# Sensor.net
KiCad netlist of a schematic drawn in Altium Designer
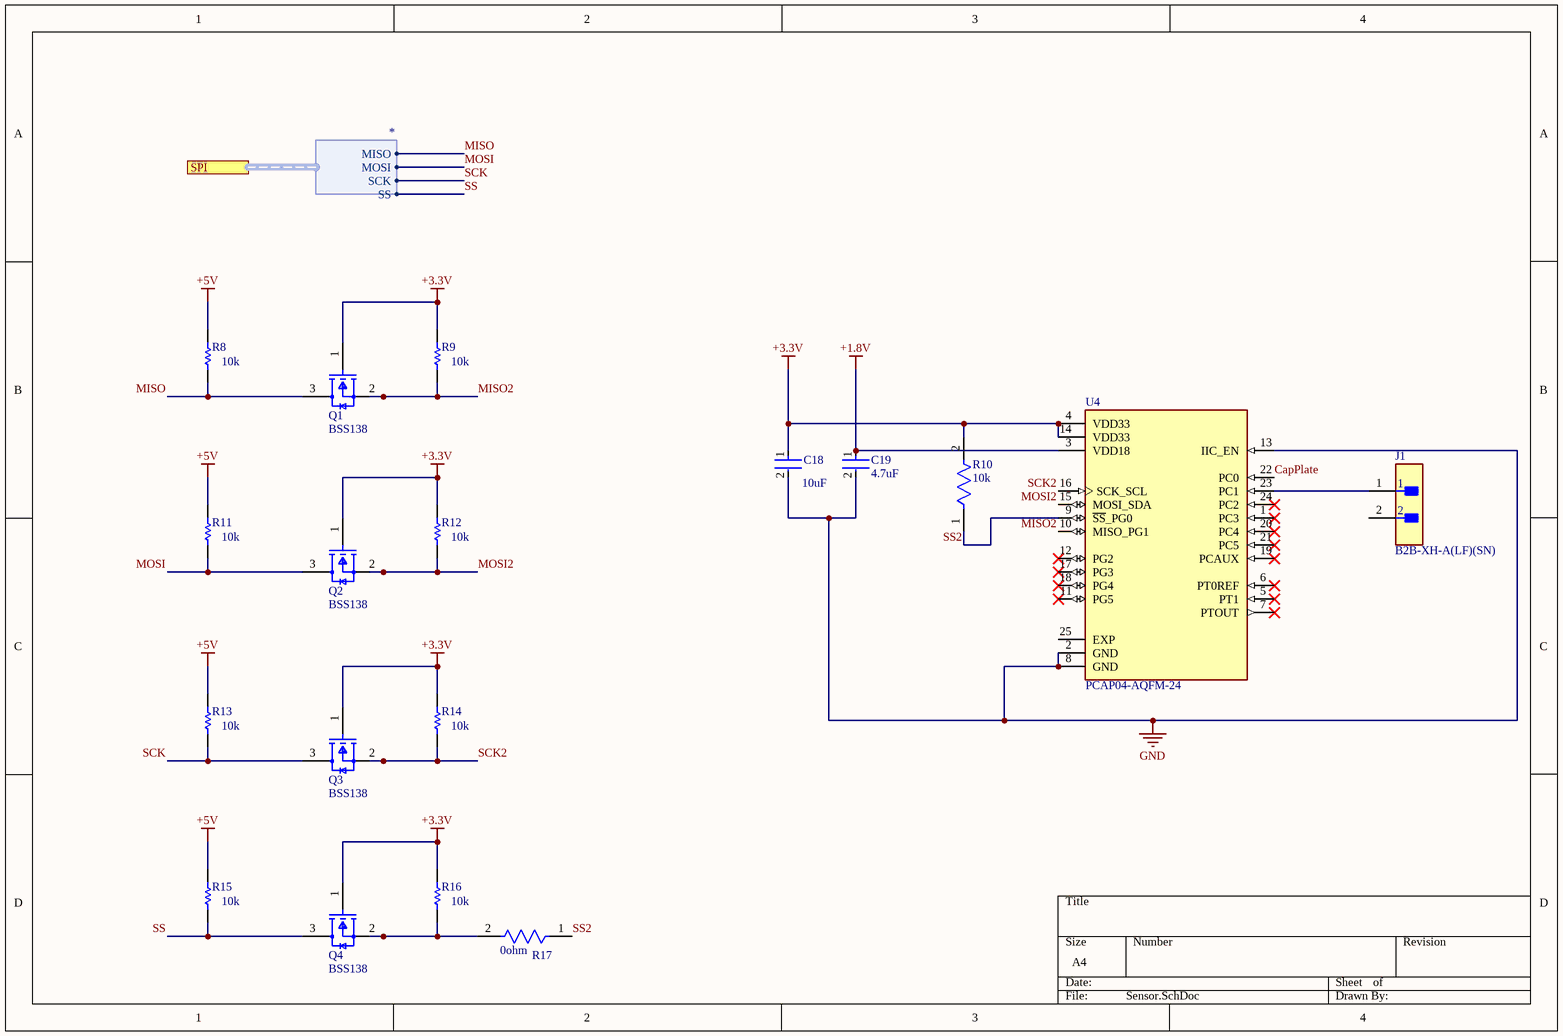
[diagram p0: Sensor.SchDoc]

(export (version "E")
  (design (tool "Eeschema 10.0.6"))
  (components
    (comp (ref "C18")
      (value "C0805C106K8PACTU")
      (footprint "FP-C0805C-DG-MFG")
      (description "CAP CER 10UF 10V X5R 0805")
      (fields
        (field (name "TOLERANCE") "10%")
        (field (name "MANUFACTURER") "Kemet")
        (field (name "CAPACITANCE") "10uF")
      )
      (libsource (lib "Altium Content Vault") (part "11868f565c42a9108669ba33697ecf6"))
    )
    (comp (ref "C19")
      (value "4.7uF")
      (footprint "FP-C0805C475K8PACTU-MFG")
      (description "CAP CER 4.7UF 10V X5R 0805")
      (fields (field (name "TOLERANCE") "10%") (field (name "VOLTAGE") "10V"))
      (libsource (lib "Altium Content Vault") (part "e9c51b7dd13d4faca003ae77663ab08"))
    )
    (comp (ref "J1")
      (value "B2B-XH-A(LF)(SN)")
      (footprint "FP-B2B-XH-A_LF_SN-MFG")
      (description "CONN HEADER VERT 2POS 2.5MM")
      (libsource (lib "Altium Content Vault") (part "3bc925449376181038e59eaffc5286c"))
    )
    (comp (ref "Q1")
      (value "BSS138")
      (footprint "FP-318-08-IPC_B")
      (description "MOSFET N-CH 50V 220MA SOT-23")
      (libsource (lib "Altium Content Vault") (part "3b9c635fedb024a5347a57b145af9cc"))
    )
    (comp (ref "Q2")
      (value "BSS138")
      (footprint "FP-318-08-IPC_B")
      (description "MOSFET N-CH 50V 220MA SOT-23")
      (libsource (lib "Altium Content Vault") (part "3b9c635fedb024a5347a57b145af9cc"))
    )
    (comp (ref "Q3")
      (value "BSS138")
      (footprint "FP-318-08-IPC_B")
      (description "MOSFET N-CH 50V 220MA SOT-23")
      (libsource (lib "Altium Content Vault") (part "3b9c635fedb024a5347a57b145af9cc"))
    )
    (comp (ref "Q4")
      (value "BSS138")
      (footprint "FP-318-08-IPC_B")
      (description "MOSFET N-CH 50V 220MA SOT-23")
      (libsource (lib "Altium Content Vault") (part "3b9c635fedb024a5347a57b145af9cc"))
    )
    (comp (ref "R8")
      (value "10k")
      (footprint "RESC3116X65X50NL20T20")
      (fields (field (name "PART NUMBER") "CRCW120610K0FKEAHP") (field (name "MANUFACTURER") "Vishay Dale"))
      (libsource (lib "Altium Content Vault") (part "RES"))
    )
    (comp (ref "R9")
      (value "10k")
      (footprint "RESC3116X65X50NL20T20")
      (fields (field (name "PART NUMBER") "CRCW120610K0FKEAHP") (field (name "MANUFACTURER") "Vishay Dale"))
      (libsource (lib "Altium Content Vault") (part "RES"))
    )
    (comp (ref "R10")
      (value "CRCW080522R0FKEA")
      (footprint "FP-CRCW0805-e3-IPC_C")
      (description "RES Thick Film, 22Ω, 1%, 0.125W, 100ppm/°C, 0805")
      (fields (field (name "RESISTANCE") "10k") (field (name "TOLERANCE") "1%"))
      (libsource (lib "Altium Content Vault") (part "1029c3af85768c4190bb7ad29bc67b5"))
    )
    (comp (ref "R11")
      (value "10k")
      (footprint "RESC3116X65X50NL20T20")
      (fields (field (name "PART NUMBER") "CRCW120610K0FKEAHP") (field (name "MANUFACTURER") "Vishay Dale"))
      (libsource (lib "Altium Content Vault") (part "RES"))
    )
    (comp (ref "R12")
      (value "10k")
      (footprint "RESC3116X65X50NL20T20")
      (fields (field (name "PART NUMBER") "CRCW120610K0FKEAHP") (field (name "MANUFACTURER") "Vishay Dale"))
      (libsource (lib "Altium Content Vault") (part "RES"))
    )
    (comp (ref "R13")
      (value "10k")
      (footprint "RESC3116X65X50NL20T20")
      (fields (field (name "PART NUMBER") "CRCW120610K0FKEAHP") (field (name "MANUFACTURER") "Vishay Dale"))
      (libsource (lib "Altium Content Vault") (part "RES"))
    )
    (comp (ref "R14")
      (value "10k")
      (footprint "RESC3116X65X50NL20T20")
      (fields (field (name "PART NUMBER") "CRCW120610K0FKEAHP") (field (name "MANUFACTURER") "Vishay Dale"))
      (libsource (lib "Altium Content Vault") (part "RES"))
    )
    (comp (ref "R15")
      (value "10k")
      (footprint "RESC3116X65X50NL20T20")
      (fields (field (name "PART NUMBER") "CRCW120610K0FKEAHP") (field (name "MANUFACTURER") "Vishay Dale"))
      (libsource (lib "Altium Content Vault") (part "RES"))
    )
    (comp (ref "R16")
      (value "10k")
      (footprint "RESC3116X65X50NL20T20")
      (fields (field (name "PART NUMBER") "CRCW120610K0FKEAHP") (field (name "MANUFACTURER") "Vishay Dale"))
      (libsource (lib "Altium Content Vault") (part "RES"))
    )
    (comp (ref "R17")
      (value "CRCW080522R0FKEA")
      (footprint "FP-CRCW0805-e3-IPC_C")
      (description "RES Thick Film, 22Ω, 1%, 0.125W, 100ppm/°C, 0805")
      (fields (field (name "RESISTANCE") "0ohm") (field (name "TOLERANCE") "1%"))
      (libsource (lib "Altium Content Vault") (part "1029c3af85768c4190bb7ad29bc67b5"))
    )
    (comp (ref "U4")
      (value "PCAP04-AQFM-24")
      (footprint "IC_PCAP04-AQFM-24")
      (description "Capacitance-to-Digital Converter 17 b IÂ²C, SPI 24-QFN (4x4)")
      (fields (field (name "MF") "ScioSense"))
      (libsource (lib "University of Moratuwa") (part "PCAP04-AQFM-24"))
    )
  )
  (nets
    (net (code "2") (name "+1.8V") (class "Default")
      (node (ref "C19") (pin "1") (pinfunction "1_1") (pintype "passive"))
      (node (ref "U4") (pin "3") (pinfunction "VDD18_3") (pintype "power_in"))
    )
    (net (code "3") (name "+3.3V") (class "Default")
      (node (ref "C18") (pin "1") (pinfunction "1_1") (pintype "passive"))
      (node (ref "Q1") (pin "1") (pinfunction "G_1") (pintype "passive"))
      (node (ref "Q2") (pin "1") (pinfunction "G_1") (pintype "passive"))
      (node (ref "Q3") (pin "1") (pinfunction "G_1") (pintype "passive"))
      (node (ref "Q4") (pin "1") (pinfunction "G_1") (pintype "passive"))
      (node (ref "R10") (pin "2") (pinfunction "2_2") (pintype "passive"))
      (node (ref "R12") (pin "2") (pinfunction "2_2") (pintype "passive"))
      (node (ref "R14") (pin "2") (pinfunction "2_2") (pintype "passive"))
      (node (ref "R16") (pin "2") (pinfunction "2_2") (pintype "passive"))
      (node (ref "R9") (pin "2") (pinfunction "2_2") (pintype "passive"))
      (node (ref "U4") (pin "14") (pinfunction "VDD33_14") (pintype "power_in"))
      (node (ref "U4") (pin "4") (pinfunction "VDD33_4") (pintype "power_in"))
    )
    (net (code "4") (name "+5V") (class "Default")
      (node (ref "R11") (pin "2") (pinfunction "2_2") (pintype "passive"))
      (node (ref "R13") (pin "2") (pinfunction "2_2") (pintype "passive"))
      (node (ref "R15") (pin "2") (pinfunction "2_2") (pintype "passive"))
      (node (ref "R8") (pin "2") (pinfunction "2_2") (pintype "passive"))
    )
    (net (code "5") (name "/CapPlate") (class "Default")
      (node (ref "U4") (pin "22") (pinfunction "PC0_22") (pintype "input"))
    )
    (net (code "6") (name "/MISO") (class "Default")
      (node (ref "Q1") (pin "3") (pinfunction "D_3") (pintype "passive"))
      (node (ref "R8") (pin "1") (pinfunction "1_1") (pintype "passive"))
    )
    (net (code "7") (name "/MISO2") (class "Default")
      (node (ref "Q1") (pin "2") (pinfunction "S_2") (pintype "passive"))
      (node (ref "R9") (pin "1") (pinfunction "1_1") (pintype "passive"))
      (node (ref "U4") (pin "10") (pinfunction "MISO_PG1_10") (pintype "bidirectional"))
    )
    (net (code "8") (name "/MOSI") (class "Default")
      (node (ref "Q2") (pin "3") (pinfunction "D_3") (pintype "passive"))
      (node (ref "R11") (pin "1") (pinfunction "1_1") (pintype "passive"))
    )
    (net (code "9") (name "/MOSI2") (class "Default")
      (node (ref "Q2") (pin "2") (pinfunction "S_2") (pintype "passive"))
      (node (ref "R12") (pin "1") (pinfunction "1_1") (pintype "passive"))
      (node (ref "U4") (pin "15") (pinfunction "MOSI_SDA_15") (pintype "bidirectional"))
    )
    (net (code "10") (name "/SCK") (class "Default")
      (node (ref "Q3") (pin "3") (pinfunction "D_3") (pintype "passive"))
      (node (ref "R13") (pin "1") (pinfunction "1_1") (pintype "passive"))
    )
    (net (code "11") (name "/SCK2") (class "Default")
      (node (ref "Q3") (pin "2") (pinfunction "S_2") (pintype "passive"))
      (node (ref "R14") (pin "1") (pinfunction "1_1") (pintype "passive"))
      (node (ref "U4") (pin "16") (pinfunction "SCK_SCL_16") (pintype "input"))
    )
    (net (code "12") (name "/SS") (class "Default")
      (node (ref "Q4") (pin "3") (pinfunction "D_3") (pintype "passive"))
      (node (ref "R15") (pin "1") (pinfunction "1_1") (pintype "passive"))
    )
    (net (code "13") (name "/SS2") (class "Default")
      (node (ref "R10") (pin "1") (pinfunction "1_1") (pintype "passive"))
      (node (ref "R17") (pin "1") (pinfunction "1_1") (pintype "passive"))
      (node (ref "U4") (pin "9") (pinfunction "~{SS}_PG0_9") (pintype "bidirectional"))
    )
    (net (code "15") (name "GND") (class "Default")
      (node (ref "C18") (pin "2") (pinfunction "2_2") (pintype "passive"))
      (node (ref "C19") (pin "2") (pinfunction "2_2") (pintype "passive"))
      (node (ref "U4") (pin "13") (pinfunction "IIC_EN_13") (pintype "input"))
      (node (ref "U4") (pin "2") (pinfunction "GND_2") (pintype "power_in"))
      (node (ref "U4") (pin "8") (pinfunction "GND_8") (pintype "power_in"))
    )
    (net (code "16") (name "Net-(Q4-S)") (class "Default")
      (node (ref "Q4") (pin "2") (pinfunction "S_2") (pintype "passive"))
      (node (ref "R16") (pin "1") (pinfunction "1_1") (pintype "passive"))
      (node (ref "R17") (pin "2") (pinfunction "2_2") (pintype "passive"))
    )
    (net (code "17") (name "Net-(U4-PC1)") (class "Default")
      (node (ref "J1") (pin "1") (pinfunction "1_1") (pintype "passive"))
      (node (ref "U4") (pin "23") (pinfunction "PC1_23") (pintype "input"))
    )
    (net (code "18") (name "unconnected-(J1-Pad2)") (class "Default")
      (node (ref "J1") (pin "2") (pinfunction "2_2") (pintype "passive"))
    )
    (net (code "19") (name "unconnected-(U4-EXP-Pad25)") (class "Default")
      (node (ref "U4") (pin "25") (pinfunction "EXP_25") (pintype "power_in"))
    )
    (net (code "20") (name "unconnected-(U4-PC2-Pad24)") (class "Default")
      (node (ref "U4") (pin "24") (pinfunction "PC2_24") (pintype "input+no_connect"))
    )
    (net (code "21") (name "unconnected-(U4-PC3-Pad1)") (class "Default")
      (node (ref "U4") (pin "1") (pinfunction "PC3_1") (pintype "input+no_connect"))
    )
    (net (code "22") (name "unconnected-(U4-PC4-Pad20)") (class "Default")
      (node (ref "U4") (pin "20") (pinfunction "PC4_20") (pintype "input+no_connect"))
    )
    (net (code "23") (name "unconnected-(U4-PC5-Pad21)") (class "Default")
      (node (ref "U4") (pin "21") (pinfunction "PC5_21") (pintype "input+no_connect"))
    )
    (net (code "24") (name "unconnected-(U4-PCAUX-Pad19)") (class "Default")
      (node (ref "U4") (pin "19") (pinfunction "PCAUX_19") (pintype "input+no_connect"))
    )
    (net (code "25") (name "unconnected-(U4-PG2-Pad12)") (class "Default")
      (node (ref "U4") (pin "12") (pinfunction "PG2_12") (pintype "bidirectional+no_connect"))
    )
    (net (code "26") (name "unconnected-(U4-PG3-Pad17)") (class "Default")
      (node (ref "U4") (pin "17") (pinfunction "PG3_17") (pintype "bidirectional+no_connect"))
    )
    (net (code "27") (name "unconnected-(U4-PG4-Pad18)") (class "Default")
      (node (ref "U4") (pin "18") (pinfunction "PG4_18") (pintype "bidirectional+no_connect"))
    )
    (net (code "28") (name "unconnected-(U4-PG5-Pad11)") (class "Default")
      (node (ref "U4") (pin "11") (pinfunction "PG5_11") (pintype "bidirectional+no_connect"))
    )
    (net (code "29") (name "unconnected-(U4-PT0REF-Pad6)") (class "Default")
      (node (ref "U4") (pin "6") (pinfunction "PT0REF_6") (pintype "input+no_connect"))
    )
    (net (code "30") (name "unconnected-(U4-PT1-Pad5)") (class "Default")
      (node (ref "U4") (pin "5") (pinfunction "PT1_5") (pintype "input+no_connect"))
    )
    (net (code "31") (name "unconnected-(U4-PTOUT-Pad7)") (class "Default")
      (node (ref "U4") (pin "7") (pinfunction "PTOUT_7") (pintype "output+no_connect"))
    )
  )
)
